# k10.net
KiCad netlist of a schematic drawn in Altium Designer
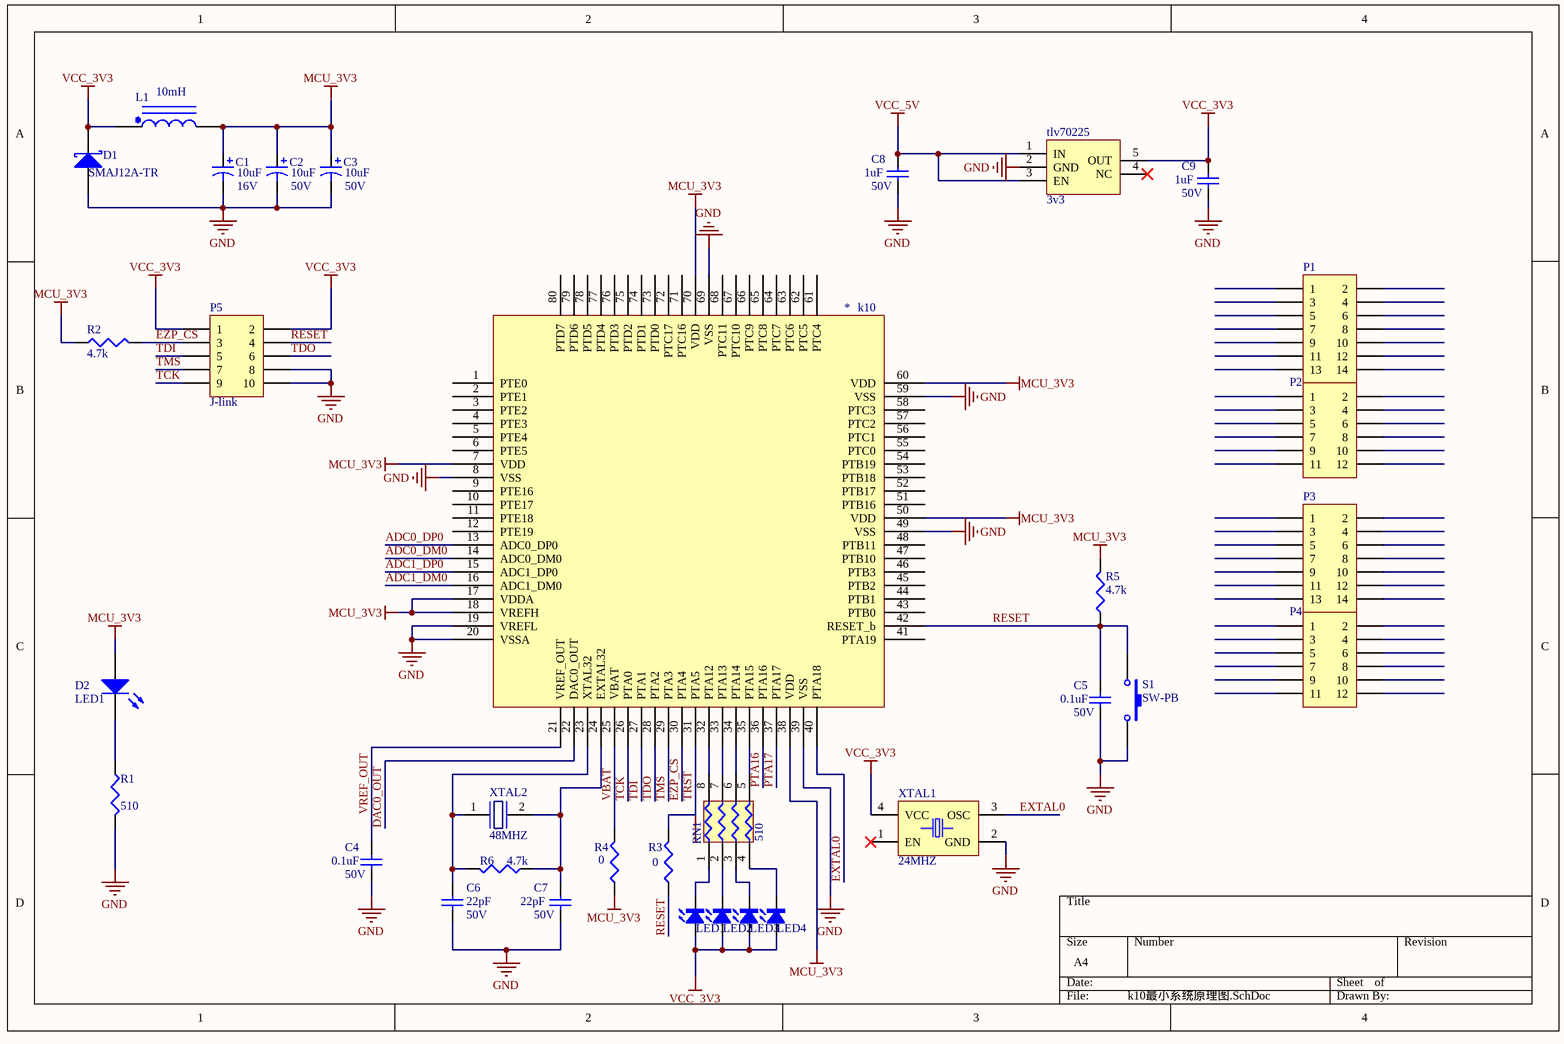
[diagram p0: k10最小系统原理图.SchDoc]

(export (version "E")
  (design (tool "Eeschema 10.0.6"))
  (components
    (comp (ref "*") (value "k10") (footprint "k10 80pin") (libsource (lib "k10 80pin") (part "Component_1")))
    (comp (ref "C1")
      (value "16V")
      (footprint "C0805")
      (description "Polarized Capacitor (Surface Mount)")
      (fields (field (name "ALTIUM_VALUE") "10uF") (field (name "PUBLISHER") "Altium Limited"))
      (libsource (lib "Miscellaneous Devices") (part "Cap Pol3"))
    )
    (comp (ref "C2")
      (value "50V")
      (footprint "C0805")
      (description "Polarized Capacitor (Surface Mount)")
      (fields (field (name "ALTIUM_VALUE") "10uF") (field (name "PUBLISHER") "Altium Limited"))
      (libsource (lib "Miscellaneous Devices") (part "Cap Pol3"))
    )
    (comp (ref "C3")
      (value "50V")
      (footprint "C0805")
      (description "Polarized Capacitor (Surface Mount)")
      (fields (field (name "ALTIUM_VALUE") "10uF") (field (name "PUBLISHER") "Altium Limited"))
      (libsource (lib "Miscellaneous Devices") (part "Cap Pol3"))
    )
    (comp (ref "C4")
      (value "50V")
      (footprint "1608[0603]")
      (description "Capacitor (Semiconductor SIM Model)")
      (fields (field (name "ALTIUM_VALUE") "0.1uF") (field (name "PUBLISHER") "Altium Limited"))
      (libsource (lib "Miscellaneous Devices") (part "Cap Semi"))
    )
    (comp (ref "C5")
      (value "50V")
      (footprint "1608[0603]")
      (description "Capacitor (Semiconductor SIM Model)")
      (fields (field (name "ALTIUM_VALUE") "0.1uF") (field (name "PUBLISHER") "Altium Limited"))
      (libsource (lib "Miscellaneous Devices") (part "Cap Semi"))
    )
    (comp (ref "C6")
      (value "50V")
      (footprint "1608[0603]")
      (description "Capacitor (Semiconductor SIM Model)")
      (fields (field (name "ALTIUM_VALUE") "22pF") (field (name "PUBLISHER") "Altium Limited"))
      (libsource (lib "Miscellaneous Devices") (part "Cap Semi"))
    )
    (comp (ref "C7")
      (value "50V")
      (footprint "1608[0603]")
      (description "Capacitor (Semiconductor SIM Model)")
      (fields (field (name "ALTIUM_VALUE") "22pF") (field (name "PUBLISHER") "Altium Limited"))
      (libsource (lib "Miscellaneous Devices") (part "Cap Semi"))
    )
    (comp (ref "C8")
      (value "50V")
      (footprint "1608[0603]")
      (description "Capacitor (Semiconductor SIM Model)")
      (fields (field (name "ALTIUM_VALUE") "1uF") (field (name "PUBLISHER") "Altium Limited"))
      (libsource (lib "Miscellaneous Devices") (part "Cap Semi"))
    )
    (comp (ref "C9")
      (value "50V")
      (footprint "1608[0603]")
      (description "Capacitor (Semiconductor SIM Model)")
      (fields (field (name "ALTIUM_VALUE") "1uF") (field (name "PUBLISHER") "Altium Limited"))
      (libsource (lib "Miscellaneous Devices") (part "Cap Semi"))
    )
    (comp (ref "D1")
      (value "SMAJ12A-TR")
      (footprint "C1206")
      (description "Schottky Diode")
      (fields (field (name "PUBLISHER") "Altium Limited"))
      (libsource (lib "Miscellaneous Devices") (part "D Schottky"))
    )
    (comp (ref "D2")
      (value "LED1")
      (footprint "6-0805")
      (description "Typical RED, GREEN, YELLOW, AMBER GaAs LED")
      (fields (field (name "PUBLISHER") "Altium Limited"))
      (libsource (lib "Miscellaneous Devices") (part "LED2"))
    )
    (comp (ref "L1")
      (value "10mH")
      (footprint "C1206")
      (description "Magnetic-Core Inductor with Winding Polarity Marking")
      (fields (field (name "Comment") "Inductor Iron Dot") (field (name "PUBLISHER") "Altium Limited"))
      (libsource (lib "Miscellaneous Devices") (part "Inductor Iron Dot"))
    )
    (comp (ref "LED1") (value "LED") (footprint "0805LED1") (libsource (lib "K60P144") (part "LED")))
    (comp (ref "LED2") (value "LED") (footprint "0805LED1") (libsource (lib "K60P144") (part "LED")))
    (comp (ref "LED3") (value "LED") (footprint "0805LED1") (libsource (lib "K60P144") (part "LED")))
    (comp (ref "LED4") (value "LED") (footprint "0805LED1") (libsource (lib "K60P144") (part "LED")))
    (comp (ref "P1")
      (value "Header 7X2")
      (footprint "HDR2X7")
      (description "Header, 7-Pin, Dual row")
      (fields (field (name "PUBLISHER") "Altium Limited"))
      (libsource (lib "Miscellaneous Connectors") (part "Header 7X2"))
    )
    (comp (ref "P2")
      (value "Header 6X2")
      (footprint "HDR2X6")
      (description "Header, 6-Pin, Dual row")
      (fields (field (name "PUBLISHER") "Altium Limited"))
      (libsource (lib "Miscellaneous Connectors") (part "Header 6X2"))
    )
    (comp (ref "P3")
      (value "Header 7X2")
      (footprint "HDR2X7")
      (description "Header, 7-Pin, Dual row")
      (fields (field (name "PUBLISHER") "Altium Limited"))
      (libsource (lib "Miscellaneous Connectors") (part "Header 7X2"))
    )
    (comp (ref "P4")
      (value "Header 6X2")
      (footprint "HDR2X6")
      (description "Header, 6-Pin, Dual row")
      (fields (field (name "PUBLISHER") "Altium Limited"))
      (libsource (lib "Miscellaneous Connectors") (part "Header 6X2"))
    )
    (comp (ref "P5")
      (value "J-link")
      (footprint "HDR2X5")
      (description "Header, 5-Pin, Dual row")
      (fields (field (name "PUBLISHER") "Altium Limited"))
      (libsource (lib "Miscellaneous Connectors") (part "Header 5X2"))
    )
    (comp (ref "R1")
      (value "510")
      (footprint "J1-0603")
      (description "Resistor")
      (fields (field (name "Comment") "Res3") (field (name "PUBLISHER") "Altium Limited"))
      (libsource (lib "Miscellaneous Devices") (part "Res3"))
    )
    (comp (ref "R2")
      (value "4.7k")
      (footprint "J1-0603")
      (description "Resistor")
      (fields (field (name "Comment") "Res3") (field (name "PUBLISHER") "Altium Limited"))
      (libsource (lib "Miscellaneous Devices") (part "Res3"))
    )
    (comp (ref "R3")
      (value "0")
      (footprint "J1-0603")
      (description "Resistor")
      (fields (field (name "Comment") "Res3") (field (name "PUBLISHER") "Altium Limited"))
      (libsource (lib "Miscellaneous Devices") (part "Res3"))
    )
    (comp (ref "R4")
      (value "0")
      (footprint "J1-0603")
      (description "Resistor")
      (fields (field (name "Comment") "Res3") (field (name "PUBLISHER") "Altium Limited"))
      (libsource (lib "Miscellaneous Devices") (part "Res3"))
    )
    (comp (ref "R5")
      (value "4.7k")
      (footprint "J1-0603")
      (description "Resistor")
      (fields (field (name "Comment") "Res3") (field (name "PUBLISHER") "Altium Limited"))
      (libsource (lib "Miscellaneous Devices") (part "Res3"))
    )
    (comp (ref "R6")
      (value "4.7k")
      (footprint "J1-0603")
      (description "Resistor")
      (fields (field (name "Comment") "Res3") (field (name "PUBLISHER") "Altium Limited"))
      (libsource (lib "Miscellaneous Devices") (part "Res3"))
    )
    (comp (ref "RN1") (value "510") (footprint "res2*4") (libsource (lib "8脚排阻") (part "Component_1")))
    (comp (ref "S1")
      (value "SW-PB")
      (footprint "SPST-2")
      (description "Switch")
      (fields (field (name "PUBLISHER") "Altium Limited"))
      (libsource (lib "Miscellaneous Devices") (part "SW-PB"))
    )
    (comp (ref "tlv70225")
      (value "3v3")
      (footprint "tlv70225")
      (libsource (lib "tlv70225") (part "Component_1"))
    )
    (comp (ref "XTAL1") (value "24MHZ") (footprint "XTAL-3225") (libsource (lib "K60P144") (part "XTAL")))
    (comp (ref "XTAL2")
      (value "48MHZ")
      (footprint "XTAL1-KHz-直插3")
      (libsource (lib "K60P144") (part "XTAL-RTC"))
    )
  )
  (nets
    (net (code "1") (name "/ADC0_DM0") (class "Default")
      (node (ref "*") (pin "14") (pinfunction "ADC0_DM0_14") (pintype "passive"))
    )
    (net (code "2") (name "/ADC0_DP0") (class "Default")
      (node (ref "*") (pin "13") (pinfunction "ADC0_DP0_13") (pintype "passive"))
    )
    (net (code "3") (name "/ADC1_DM0") (class "Default")
      (node (ref "*") (pin "16") (pinfunction "ADC1_DM0_16") (pintype "passive"))
    )
    (net (code "4") (name "/ADC1_DP0") (class "Default")
      (node (ref "*") (pin "15") (pinfunction "ADC1_DP0_15") (pintype "passive"))
    )
    (net (code "5") (name "/DAC0_OUT") (class "Default")
      (node (ref "*") (pin "22") (pinfunction "DAC0_OUT_22") (pintype "passive"))
    )
    (net (code "6") (name "/EXTAL0") (class "Default")
      (node (ref "*") (pin "40") (pinfunction "PTA18_40") (pintype "passive"))
      (node (ref "XTAL1") (pin "3") (pinfunction "OSC_3") (pintype "passive"))
    )
    (net (code "7") (name "/EZP_CS") (class "Default")
      (node (ref "*") (pin "30") (pinfunction "PTA4_30") (pintype "passive"))
      (node (ref "P5") (pin "3") (pinfunction "3_3") (pintype "passive"))
      (node (ref "R2") (pin "2") (pinfunction "2_2") (pintype "passive"))
    )
    (net (code "8") (name "/PTA16") (class "Default")
      (node (ref "*") (pin "36") (pinfunction "PTA16_36") (pintype "passive"))
    )
    (net (code "9") (name "/PTA17") (class "Default")
      (node (ref "*") (pin "37") (pinfunction "PTA17_37") (pintype "passive"))
    )
    (net (code "10") (name "/RESET") (class "Default")
      (node (ref "*") (pin "42") (pinfunction "RESET_b_42") (pintype "passive"))
      (node (ref "C5") (pin "2") (pinfunction "2_2") (pintype "passive"))
      (node (ref "P5") (pin "4") (pinfunction "4_4") (pintype "passive"))
      (node (ref "R3") (pin "1") (pinfunction "1_1") (pintype "passive"))
      (node (ref "R5") (pin "1") (pinfunction "1_1") (pintype "passive"))
      (node (ref "S1") (pin "1") (pinfunction "1_1") (pintype "passive"))
    )
    (net (code "11") (name "/TCK") (class "Default")
      (node (ref "*") (pin "26") (pinfunction "PTA0_26") (pintype "passive"))
      (node (ref "P5") (pin "9") (pinfunction "9_9") (pintype "passive"))
    )
    (net (code "12") (name "/TDI") (class "Default")
      (node (ref "*") (pin "27") (pinfunction "PTA1_27") (pintype "passive"))
      (node (ref "P5") (pin "5") (pinfunction "5_5") (pintype "passive"))
    )
    (net (code "13") (name "/TDO") (class "Default")
      (node (ref "*") (pin "28") (pinfunction "PTA2_28") (pintype "passive"))
      (node (ref "P5") (pin "6") (pinfunction "6_6") (pintype "passive"))
    )
    (net (code "14") (name "/TMS") (class "Default")
      (node (ref "*") (pin "29") (pinfunction "PTA3_29") (pintype "passive"))
      (node (ref "P5") (pin "7") (pinfunction "7_7") (pintype "passive"))
    )
    (net (code "15") (name "/TRST") (class "Default")
      (node (ref "*") (pin "31") (pinfunction "PTA5_31") (pintype "passive"))
      (node (ref "R3") (pin "2") (pinfunction "2_2") (pintype "passive"))
    )
    (net (code "16") (name "/VBAT") (class "Default")
      (node (ref "*") (pin "25") (pinfunction "VBAT_25") (pintype "passive"))
      (node (ref "R4") (pin "2") (pinfunction "2_2") (pintype "passive"))
    )
    (net (code "17") (name "/VREF_OUT") (class "Default")
      (node (ref "*") (pin "21") (pinfunction "VREF_OUT_21") (pintype "passive"))
      (node (ref "C4") (pin "2") (pinfunction "2_2") (pintype "passive"))
    )
    (net (code "18") (name "GND") (class "Default")
      (node (ref "*") (pin "19") (pinfunction "VREFL_19") (pintype "passive"))
      (node (ref "*") (pin "20") (pinfunction "VSSA_20") (pintype "passive"))
      (node (ref "*") (pin "39") (pinfunction "VSS_39") (pintype "passive"))
      (node (ref "*") (pin "49") (pinfunction "VSS_49") (pintype "passive"))
      (node (ref "*") (pin "59") (pinfunction "VSS_59") (pintype "passive"))
      (node (ref "*") (pin "69") (pinfunction "VSS_69") (pintype "passive"))
      (node (ref "*") (pin "8") (pinfunction "VSS_8") (pintype "passive"))
      (node (ref "C1") (pin "2") (pinfunction "2_2") (pintype "passive"))
      (node (ref "C2") (pin "2") (pinfunction "2_2") (pintype "passive"))
      (node (ref "C3") (pin "2") (pinfunction "2_2") (pintype "passive"))
      (node (ref "C4") (pin "1") (pinfunction "1_1") (pintype "passive"))
      (node (ref "C5") (pin "1") (pinfunction "1_1") (pintype "passive"))
      (node (ref "C6") (pin "1") (pinfunction "1_1") (pintype "passive"))
      (node (ref "C7") (pin "1") (pinfunction "1_1") (pintype "passive"))
      (node (ref "C8") (pin "1") (pinfunction "1_1") (pintype "passive"))
      (node (ref "C9") (pin "1") (pinfunction "1_1") (pintype "passive"))
      (node (ref "D1") (pin "1") (pinfunction "A_1") (pintype "passive"))
      (node (ref "P5") (pin "10") (pinfunction "10_10") (pintype "passive"))
      (node (ref "P5") (pin "8") (pinfunction "8_8") (pintype "passive"))
      (node (ref "R1") (pin "2") (pinfunction "2_2") (pintype "passive"))
      (node (ref "S1") (pin "2") (pinfunction "2_2") (pintype "passive"))
      (node (ref "XTAL1") (pin "2") (pinfunction "GND_2") (pintype "passive"))
      (node (ref "tlv70225") (pin "2") (pinfunction "GND_2") (pintype "passive"))
    )
    (net (code "19") (name "MCU_3V3") (class "Default")
      (node (ref "*") (pin "17") (pinfunction "VDDA_17") (pintype "passive"))
      (node (ref "*") (pin "18") (pinfunction "VREFH_18") (pintype "passive"))
      (node (ref "*") (pin "38") (pinfunction "VDD_38") (pintype "passive"))
      (node (ref "*") (pin "50") (pinfunction "VDD_50") (pintype "passive"))
      (node (ref "*") (pin "60") (pinfunction "VDD_60") (pintype "passive"))
      (node (ref "*") (pin "7") (pinfunction "VDD_7") (pintype "passive"))
      (node (ref "*") (pin "70") (pinfunction "VDD_70") (pintype "passive"))
      (node (ref "C1") (pin "1") (pinfunction "1_1") (pintype "passive"))
      (node (ref "C2") (pin "1") (pinfunction "1_1") (pintype "passive"))
      (node (ref "C3") (pin "1") (pinfunction "1_1") (pintype "passive"))
      (node (ref "D2") (pin "1") (pinfunction "A_1") (pintype "passive"))
      (node (ref "L1") (pin "2") (pinfunction "2_2") (pintype "passive"))
      (node (ref "R2") (pin "1") (pinfunction "1_1") (pintype "passive"))
      (node (ref "R4") (pin "1") (pinfunction "1_1") (pintype "passive"))
      (node (ref "R5") (pin "2") (pinfunction "2_2") (pintype "passive"))
    )
    (net (code "20") (name "Net-(*-EXTAL32)") (class "Default")
      (node (ref "*") (pin "24") (pinfunction "EXTAL32_24") (pintype "passive"))
      (node (ref "C7") (pin "2") (pinfunction "2_2") (pintype "passive"))
      (node (ref "R6") (pin "1") (pinfunction "1_1") (pintype "passive"))
      (node (ref "XTAL2") (pin "2") (pintype "passive"))
    )
    (net (code "21") (name "Net-(*-PTA12)") (class "Default")
      (node (ref "*") (pin "32") (pinfunction "PTA12_32") (pintype "passive"))
      (node (ref "RN1") (pin "8") (pinfunction "8_8") (pintype "passive"))
    )
    (net (code "22") (name "Net-(*-PTA13)") (class "Default")
      (node (ref "*") (pin "33") (pinfunction "PTA13_33") (pintype "passive"))
      (node (ref "RN1") (pin "7") (pinfunction "7_7") (pintype "passive"))
    )
    (net (code "23") (name "Net-(*-PTA14)") (class "Default")
      (node (ref "*") (pin "34") (pinfunction "PTA14_34") (pintype "passive"))
      (node (ref "RN1") (pin "6") (pinfunction "6_6") (pintype "passive"))
    )
    (net (code "24") (name "Net-(*-PTA15)") (class "Default")
      (node (ref "*") (pin "35") (pinfunction "PTA15_35") (pintype "passive"))
      (node (ref "RN1") (pin "5") (pinfunction "5_5") (pintype "passive"))
    )
    (net (code "25") (name "Net-(*-XTAL32)") (class "Default")
      (node (ref "*") (pin "23") (pinfunction "XTAL32_23") (pintype "passive"))
      (node (ref "C6") (pin "2") (pinfunction "2_2") (pintype "passive"))
      (node (ref "R6") (pin "2") (pinfunction "2_2") (pintype "passive"))
      (node (ref "XTAL2") (pin "1") (pintype "power_in"))
    )
    (net (code "26") (name "Net-(D2-K)") (class "Default")
      (node (ref "D2") (pin "2") (pinfunction "K_2") (pintype "passive"))
      (node (ref "R1") (pin "1") (pinfunction "1_1") (pintype "passive"))
    )
    (net (code "27") (name "Net-(LED1-A)") (class "Default")
      (node (ref "LED1") (pin "2") (pinfunction "A_2") (pintype "passive"))
      (node (ref "RN1") (pin "1") (pinfunction "1_1") (pintype "passive"))
    )
    (net (code "28") (name "Net-(LED2-A)") (class "Default")
      (node (ref "LED2") (pin "2") (pinfunction "A_2") (pintype "passive"))
      (node (ref "RN1") (pin "2") (pinfunction "2_2") (pintype "passive"))
    )
    (net (code "29") (name "Net-(LED3-A)") (class "Default")
      (node (ref "LED3") (pin "2") (pinfunction "A_2") (pintype "passive"))
      (node (ref "RN1") (pin "3") (pinfunction "3_3") (pintype "passive"))
    )
    (net (code "30") (name "Net-(LED4-A)") (class "Default")
      (node (ref "LED4") (pin "2") (pinfunction "A_2") (pintype "passive"))
      (node (ref "RN1") (pin "4") (pinfunction "4_4") (pintype "passive"))
    )
    (net (code "31") (name "VCC_3V3") (class "Default")
      (node (ref "C9") (pin "2") (pinfunction "2_2") (pintype "passive"))
      (node (ref "D1") (pin "2") (pinfunction "K_2") (pintype "passive"))
      (node (ref "L1") (pin "1") (pinfunction "1_1") (pintype "passive"))
      (node (ref "LED1") (pin "1") (pinfunction "K_1") (pintype "passive"))
      (node (ref "LED2") (pin "1") (pinfunction "K_1") (pintype "passive"))
      (node (ref "LED3") (pin "1") (pinfunction "K_1") (pintype "passive"))
      (node (ref "LED4") (pin "1") (pinfunction "K_1") (pintype "passive"))
      (node (ref "P5") (pin "1") (pinfunction "1_1") (pintype "passive"))
      (node (ref "P5") (pin "2") (pinfunction "2_2") (pintype "passive"))
      (node (ref "XTAL1") (pin "4") (pinfunction "VCC_4") (pintype "power_in"))
      (node (ref "tlv70225") (pin "5") (pinfunction "OUT_5") (pintype "passive"))
    )
    (net (code "32") (name "VCC_5V") (class "Default")
      (node (ref "C8") (pin "2") (pinfunction "2_2") (pintype "passive"))
      (node (ref "tlv70225") (pin "1") (pinfunction "IN_1") (pintype "passive"))
      (node (ref "tlv70225") (pin "3") (pinfunction "EN_3") (pintype "passive"))
    )
    (net (code "33") (name "unconnected-(*-PTA19-Pad41)") (class "Default")
      (node (ref "*") (pin "41") (pinfunction "PTA19_41") (pintype "passive"))
    )
    (net (code "34") (name "unconnected-(*-PTB0-Pad43)") (class "Default")
      (node (ref "*") (pin "43") (pinfunction "PTB0_43") (pintype "passive"))
    )
    (net (code "35") (name "unconnected-(*-PTB1-Pad44)") (class "Default")
      (node (ref "*") (pin "44") (pinfunction "PTB1_44") (pintype "passive"))
    )
    (net (code "36") (name "unconnected-(*-PTB2-Pad45)") (class "Default")
      (node (ref "*") (pin "45") (pinfunction "PTB2_45") (pintype "passive"))
    )
    (net (code "37") (name "unconnected-(*-PTB3-Pad46)") (class "Default")
      (node (ref "*") (pin "46") (pinfunction "PTB3_46") (pintype "passive"))
    )
    (net (code "38") (name "unconnected-(*-PTB10-Pad47)") (class "Default")
      (node (ref "*") (pin "47") (pinfunction "PTB10_47") (pintype "passive"))
    )
    (net (code "39") (name "unconnected-(*-PTB11-Pad48)") (class "Default")
      (node (ref "*") (pin "48") (pinfunction "PTB11_48") (pintype "passive"))
    )
    (net (code "40") (name "unconnected-(*-PTB16-Pad51)") (class "Default")
      (node (ref "*") (pin "51") (pinfunction "PTB16_51") (pintype "passive"))
    )
    (net (code "41") (name "unconnected-(*-PTB17-Pad52)") (class "Default")
      (node (ref "*") (pin "52") (pinfunction "PTB17_52") (pintype "passive"))
    )
    (net (code "42") (name "unconnected-(*-PTB18-Pad53)") (class "Default")
      (node (ref "*") (pin "53") (pinfunction "PTB18_53") (pintype "passive"))
    )
    (net (code "43") (name "unconnected-(*-PTB19-Pad54)") (class "Default")
      (node (ref "*") (pin "54") (pinfunction "PTB19_54") (pintype "passive"))
    )
    (net (code "44") (name "unconnected-(*-PTC0-Pad55)") (class "Default")
      (node (ref "*") (pin "55") (pinfunction "PTC0_55") (pintype "passive"))
    )
    (net (code "45") (name "unconnected-(*-PTC1-Pad56)") (class "Default")
      (node (ref "*") (pin "56") (pinfunction "PTC1_56") (pintype "passive"))
    )
    (net (code "46") (name "unconnected-(*-PTC2-Pad57)") (class "Default")
      (node (ref "*") (pin "57") (pinfunction "PTC2_57") (pintype "passive"))
    )
    (net (code "47") (name "unconnected-(*-PTC3-Pad58)") (class "Default")
      (node (ref "*") (pin "58") (pinfunction "PTC3_58") (pintype "passive"))
    )
    (net (code "48") (name "unconnected-(*-PTC4-Pad61)") (class "Default")
      (node (ref "*") (pin "61") (pinfunction "PTC4_61") (pintype "passive"))
    )
    (net (code "49") (name "unconnected-(*-PTC5-Pad62)") (class "Default")
      (node (ref "*") (pin "62") (pinfunction "PTC5_62") (pintype "passive"))
    )
    (net (code "50") (name "unconnected-(*-PTC6-Pad63)") (class "Default")
      (node (ref "*") (pin "63") (pinfunction "PTC6_63") (pintype "passive"))
    )
    (net (code "51") (name "unconnected-(*-PTC7-Pad64)") (class "Default")
      (node (ref "*") (pin "64") (pinfunction "PTC7_64") (pintype "passive"))
    )
    (net (code "52") (name "unconnected-(*-PTC8-Pad65)") (class "Default")
      (node (ref "*") (pin "65") (pinfunction "PTC8_65") (pintype "passive"))
    )
    (net (code "53") (name "unconnected-(*-PTC9-Pad66)") (class "Default")
      (node (ref "*") (pin "66") (pinfunction "PTC9_66") (pintype "passive"))
    )
    (net (code "54") (name "unconnected-(*-PTC10-Pad67)") (class "Default")
      (node (ref "*") (pin "67") (pinfunction "PTC10_67") (pintype "passive"))
    )
    (net (code "55") (name "unconnected-(*-PTC11-Pad68)") (class "Default")
      (node (ref "*") (pin "68") (pinfunction "PTC11_68") (pintype "passive"))
    )
    (net (code "56") (name "unconnected-(*-PTC16-Pad71)") (class "Default")
      (node (ref "*") (pin "71") (pinfunction "PTC16_71") (pintype "passive"))
    )
    (net (code "57") (name "unconnected-(*-PTC17-Pad72)") (class "Default")
      (node (ref "*") (pin "72") (pinfunction "PTC17_72") (pintype "passive"))
    )
    (net (code "58") (name "unconnected-(*-PTD0-Pad73)") (class "Default")
      (node (ref "*") (pin "73") (pinfunction "PTD0_73") (pintype "passive"))
    )
    (net (code "59") (name "unconnected-(*-PTD1-Pad74)") (class "Default")
      (node (ref "*") (pin "74") (pinfunction "PTD1_74") (pintype "passive"))
    )
    (net (code "60") (name "unconnected-(*-PTD2-Pad75)") (class "Default")
      (node (ref "*") (pin "75") (pinfunction "PTD2_75") (pintype "passive"))
    )
    (net (code "61") (name "unconnected-(*-PTD3-Pad76)") (class "Default")
      (node (ref "*") (pin "76") (pinfunction "PTD3_76") (pintype "passive"))
    )
    (net (code "62") (name "unconnected-(*-PTD4-Pad77)") (class "Default")
      (node (ref "*") (pin "77") (pinfunction "PTD4_77") (pintype "passive"))
    )
    (net (code "63") (name "unconnected-(*-PTD5-Pad78)") (class "Default")
      (node (ref "*") (pin "78") (pinfunction "PTD5_78") (pintype "passive"))
    )
    (net (code "64") (name "unconnected-(*-PTD6-Pad79)") (class "Default")
      (node (ref "*") (pin "79") (pinfunction "PTD6_79") (pintype "passive"))
    )
    (net (code "65") (name "unconnected-(*-PTD7-Pad80)") (class "Default")
      (node (ref "*") (pin "80") (pinfunction "PTD7_80") (pintype "passive"))
    )
    (net (code "66") (name "unconnected-(*-PTE0-Pad1)") (class "Default")
      (node (ref "*") (pin "1") (pinfunction "PTE0_1") (pintype "passive"))
    )
    (net (code "67") (name "unconnected-(*-PTE1-Pad2)") (class "Default")
      (node (ref "*") (pin "2") (pinfunction "PTE1_2") (pintype "passive"))
    )
    (net (code "68") (name "unconnected-(*-PTE2-Pad3)") (class "Default")
      (node (ref "*") (pin "3") (pinfunction "PTE2_3") (pintype "passive"))
    )
    (net (code "69") (name "unconnected-(*-PTE3-Pad4)") (class "Default")
      (node (ref "*") (pin "4") (pinfunction "PTE3_4") (pintype "passive"))
    )
    (net (code "70") (name "unconnected-(*-PTE4-Pad5)") (class "Default")
      (node (ref "*") (pin "5") (pinfunction "PTE4_5") (pintype "passive"))
    )
    (net (code "71") (name "unconnected-(*-PTE5-Pad6)") (class "Default")
      (node (ref "*") (pin "6") (pinfunction "PTE5_6") (pintype "passive"))
    )
    (net (code "72") (name "unconnected-(*-PTE16-Pad9)") (class "Default")
      (node (ref "*") (pin "9") (pinfunction "PTE16_9") (pintype "passive"))
    )
    (net (code "73") (name "unconnected-(*-PTE17-Pad10)") (class "Default")
      (node (ref "*") (pin "10") (pinfunction "PTE17_10") (pintype "passive"))
    )
    (net (code "74") (name "unconnected-(*-PTE18-Pad11)") (class "Default")
      (node (ref "*") (pin "11") (pinfunction "PTE18_11") (pintype "passive"))
    )
    (net (code "75") (name "unconnected-(*-PTE19-Pad12)") (class "Default")
      (node (ref "*") (pin "12") (pinfunction "PTE19_12") (pintype "passive"))
    )
    (net (code "76") (name "unconnected-(P1-Pad1)") (class "Default")
      (node (ref "P1") (pin "1") (pinfunction "1_1") (pintype "passive"))
    )
    (net (code "77") (name "unconnected-(P1-Pad2)") (class "Default")
      (node (ref "P1") (pin "2") (pinfunction "2_2") (pintype "passive"))
    )
    (net (code "78") (name "unconnected-(P1-Pad3)") (class "Default")
      (node (ref "P1") (pin "3") (pinfunction "3_3") (pintype "passive"))
    )
    (net (code "79") (name "unconnected-(P1-Pad4)") (class "Default")
      (node (ref "P1") (pin "4") (pinfunction "4_4") (pintype "passive"))
    )
    (net (code "80") (name "unconnected-(P1-Pad5)") (class "Default")
      (node (ref "P1") (pin "5") (pinfunction "5_5") (pintype "passive"))
    )
    (net (code "81") (name "unconnected-(P1-Pad6)") (class "Default")
      (node (ref "P1") (pin "6") (pinfunction "6_6") (pintype "passive"))
    )
    (net (code "82") (name "unconnected-(P1-Pad7)") (class "Default")
      (node (ref "P1") (pin "7") (pinfunction "7_7") (pintype "passive"))
    )
    (net (code "83") (name "unconnected-(P1-Pad8)") (class "Default")
      (node (ref "P1") (pin "8") (pinfunction "8_8") (pintype "passive"))
    )
    (net (code "84") (name "unconnected-(P1-Pad9)") (class "Default")
      (node (ref "P1") (pin "9") (pinfunction "9_9") (pintype "passive"))
    )
    (net (code "85") (name "unconnected-(P1-Pad10)") (class "Default")
      (node (ref "P1") (pin "10") (pinfunction "10_10") (pintype "passive"))
    )
    (net (code "86") (name "unconnected-(P1-Pad11)") (class "Default")
      (node (ref "P1") (pin "11") (pinfunction "11_11") (pintype "passive"))
    )
    (net (code "87") (name "unconnected-(P1-Pad12)") (class "Default")
      (node (ref "P1") (pin "12") (pinfunction "12_12") (pintype "passive"))
    )
    (net (code "88") (name "unconnected-(P1-Pad13)") (class "Default")
      (node (ref "P1") (pin "13") (pinfunction "13_13") (pintype "passive"))
    )
    (net (code "89") (name "unconnected-(P1-Pad14)") (class "Default")
      (node (ref "P1") (pin "14") (pinfunction "14_14") (pintype "passive"))
    )
    (net (code "90") (name "unconnected-(P2-Pad1)") (class "Default")
      (node (ref "P2") (pin "1") (pinfunction "1_1") (pintype "passive"))
    )
    (net (code "91") (name "unconnected-(P2-Pad2)") (class "Default")
      (node (ref "P2") (pin "2") (pinfunction "2_2") (pintype "passive"))
    )
    (net (code "92") (name "unconnected-(P2-Pad3)") (class "Default")
      (node (ref "P2") (pin "3") (pinfunction "3_3") (pintype "passive"))
    )
    (net (code "93") (name "unconnected-(P2-Pad4)") (class "Default")
      (node (ref "P2") (pin "4") (pinfunction "4_4") (pintype "passive"))
    )
    (net (code "94") (name "unconnected-(P2-Pad5)") (class "Default")
      (node (ref "P2") (pin "5") (pinfunction "5_5") (pintype "passive"))
    )
    (net (code "95") (name "unconnected-(P2-Pad6)") (class "Default")
      (node (ref "P2") (pin "6") (pinfunction "6_6") (pintype "passive"))
    )
    (net (code "96") (name "unconnected-(P2-Pad7)") (class "Default")
      (node (ref "P2") (pin "7") (pinfunction "7_7") (pintype "passive"))
    )
    (net (code "97") (name "unconnected-(P2-Pad8)") (class "Default")
      (node (ref "P2") (pin "8") (pinfunction "8_8") (pintype "passive"))
    )
    (net (code "98") (name "unconnected-(P2-Pad9)") (class "Default")
      (node (ref "P2") (pin "9") (pinfunction "9_9") (pintype "passive"))
    )
    (net (code "99") (name "unconnected-(P2-Pad10)") (class "Default")
      (node (ref "P2") (pin "10") (pinfunction "10_10") (pintype "passive"))
    )
    (net (code "100") (name "unconnected-(P2-Pad11)") (class "Default")
      (node (ref "P2") (pin "11") (pinfunction "11_11") (pintype "passive"))
    )
    (net (code "101") (name "unconnected-(P2-Pad12)") (class "Default")
      (node (ref "P2") (pin "12") (pinfunction "12_12") (pintype "passive"))
    )
    (net (code "102") (name "unconnected-(P3-Pad1)") (class "Default")
      (node (ref "P3") (pin "1") (pinfunction "1_1") (pintype "passive"))
    )
    (net (code "103") (name "unconnected-(P3-Pad2)") (class "Default")
      (node (ref "P3") (pin "2") (pinfunction "2_2") (pintype "passive"))
    )
    (net (code "104") (name "unconnected-(P3-Pad3)") (class "Default")
      (node (ref "P3") (pin "3") (pinfunction "3_3") (pintype "passive"))
    )
    (net (code "105") (name "unconnected-(P3-Pad4)") (class "Default")
      (node (ref "P3") (pin "4") (pinfunction "4_4") (pintype "passive"))
    )
    (net (code "106") (name "unconnected-(P3-Pad5)") (class "Default")
      (node (ref "P3") (pin "5") (pinfunction "5_5") (pintype "passive"))
    )
    (net (code "107") (name "unconnected-(P3-Pad6)") (class "Default")
      (node (ref "P3") (pin "6") (pinfunction "6_6") (pintype "passive"))
    )
    (net (code "108") (name "unconnected-(P3-Pad7)") (class "Default")
      (node (ref "P3") (pin "7") (pinfunction "7_7") (pintype "passive"))
    )
    (net (code "109") (name "unconnected-(P3-Pad8)") (class "Default")
      (node (ref "P3") (pin "8") (pinfunction "8_8") (pintype "passive"))
    )
    (net (code "110") (name "unconnected-(P3-Pad9)") (class "Default")
      (node (ref "P3") (pin "9") (pinfunction "9_9") (pintype "passive"))
    )
    (net (code "111") (name "unconnected-(P3-Pad10)") (class "Default")
      (node (ref "P3") (pin "10") (pinfunction "10_10") (pintype "passive"))
    )
    (net (code "112") (name "unconnected-(P3-Pad11)") (class "Default")
      (node (ref "P3") (pin "11") (pinfunction "11_11") (pintype "passive"))
    )
    (net (code "113") (name "unconnected-(P3-Pad12)") (class "Default")
      (node (ref "P3") (pin "12") (pinfunction "12_12") (pintype "passive"))
    )
    (net (code "114") (name "unconnected-(P3-Pad13)") (class "Default")
      (node (ref "P3") (pin "13") (pinfunction "13_13") (pintype "passive"))
    )
    (net (code "115") (name "unconnected-(P3-Pad14)") (class "Default")
      (node (ref "P3") (pin "14") (pinfunction "14_14") (pintype "passive"))
    )
    (net (code "116") (name "unconnected-(P4-Pad1)") (class "Default")
      (node (ref "P4") (pin "1") (pinfunction "1_1") (pintype "passive"))
    )
    (net (code "117") (name "unconnected-(P4-Pad2)") (class "Default")
      (node (ref "P4") (pin "2") (pinfunction "2_2") (pintype "passive"))
    )
    (net (code "118") (name "unconnected-(P4-Pad3)") (class "Default")
      (node (ref "P4") (pin "3") (pinfunction "3_3") (pintype "passive"))
    )
    (net (code "119") (name "unconnected-(P4-Pad4)") (class "Default")
      (node (ref "P4") (pin "4") (pinfunction "4_4") (pintype "passive"))
    )
    (net (code "120") (name "unconnected-(P4-Pad5)") (class "Default")
      (node (ref "P4") (pin "5") (pinfunction "5_5") (pintype "passive"))
    )
    (net (code "121") (name "unconnected-(P4-Pad6)") (class "Default")
      (node (ref "P4") (pin "6") (pinfunction "6_6") (pintype "passive"))
    )
    (net (code "122") (name "unconnected-(P4-Pad7)") (class "Default")
      (node (ref "P4") (pin "7") (pinfunction "7_7") (pintype "passive"))
    )
    (net (code "123") (name "unconnected-(P4-Pad8)") (class "Default")
      (node (ref "P4") (pin "8") (pinfunction "8_8") (pintype "passive"))
    )
    (net (code "124") (name "unconnected-(P4-Pad9)") (class "Default")
      (node (ref "P4") (pin "9") (pinfunction "9_9") (pintype "passive"))
    )
    (net (code "125") (name "unconnected-(P4-Pad10)") (class "Default")
      (node (ref "P4") (pin "10") (pinfunction "10_10") (pintype "passive"))
    )
    (net (code "126") (name "unconnected-(P4-Pad11)") (class "Default")
      (node (ref "P4") (pin "11") (pinfunction "11_11") (pintype "passive"))
    )
    (net (code "127") (name "unconnected-(P4-Pad12)") (class "Default")
      (node (ref "P4") (pin "12") (pinfunction "12_12") (pintype "passive"))
    )
    (net (code "128") (name "unconnected-(XTAL1-EN-Pad1)") (class "Default")
      (node (ref "XTAL1") (pin "1") (pinfunction "EN_1") (pintype "passive+no_connect"))
    )
    (net (code "129") (name "unconnected-(tlv70225-NC-Pad4)") (class "Default")
      (node (ref "tlv70225") (pin "4") (pinfunction "NC_4") (pintype "passive+no_connect"))
    )
  )
)
